# Relay_Driver.net
KiCad netlist of a schematic drawn in Altium Designer
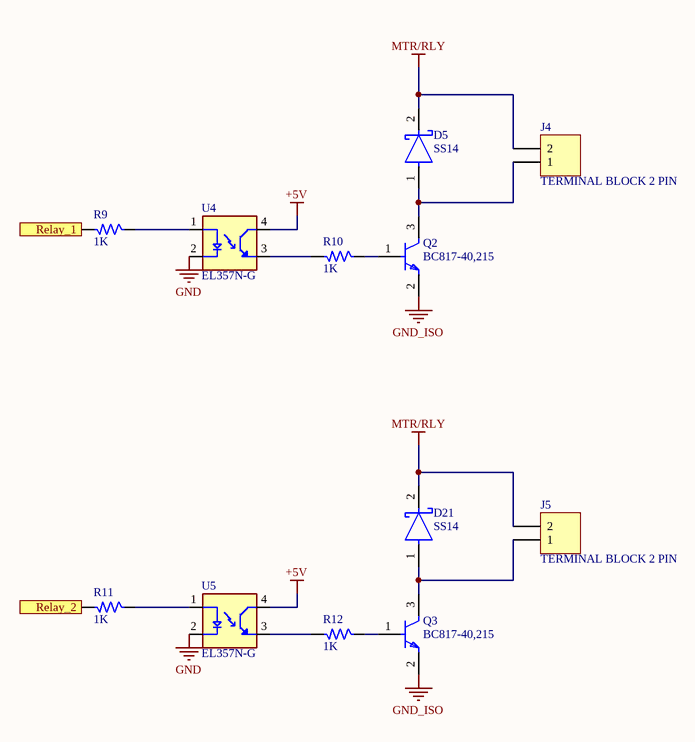
[diagram p0: Relay Driver.SchDoc]

(export (version "E")
  (design (tool "Eeschema 10.0.6"))
  (components
    (comp (ref "D5")
      (value "SS14")
      (footprint "FP-403AE-MFG")
      (description "DIODE SCHOTTKY 40V 1A SMA")
      (fields
        (field (name "MANUFACTURER") "ON Semiconductor")
        (field (name "OCTOPART") "https://octopart.com/ss14-on+semiconductor-29205033")
      )
      (libsource (lib "TAREKPCBLIB") (part "SS14"))
    )
    (comp (ref "D21")
      (value "SS14")
      (footprint "FP-403AE-MFG")
      (description "DIODE SCHOTTKY 40V 1A SMA")
      (fields
        (field (name "MANUFACTURER") "ON Semiconductor")
        (field (name "OCTOPART") "https://octopart.com/ss14-on+semiconductor-29205033")
      )
      (libsource (lib "TAREKPCBLIB") (part "SS14"))
    )
    (comp (ref "J4")
      (value "TERMINAL BLOCK 2 PIN")
      (footprint "CON2_P196_1729128_TH_ST")
      (description "2 Pins, 1 Row 5mm Pitch, straight Connector, male")
      (fields
        (field (name "MANUFACTURER") "Phoenix Contact")
        (field (name "MANUFACTURER PART NUMBER") "MKDSN1,5/2")
      )
      (libsource (lib "ESTEEMPCBLIB") (part "CON-TB_2X1-196-ST-TH"))
    )
    (comp (ref "J5")
      (value "TERMINAL BLOCK 2 PIN")
      (footprint "CON2_P196_1729128_TH_ST")
      (description "2 Pins, 1 Row 5mm Pitch, straight Connector, male")
      (fields
        (field (name "MANUFACTURER") "Phoenix Contact")
        (field (name "MANUFACTURER PART NUMBER") "MKDSN1,5/2")
      )
      (libsource (lib "ESTEEMPCBLIB") (part "CON-TB_2X1-196-ST-TH"))
    )
    (comp (ref "Q2")
      (value "BC817-40,215")
      (footprint "FP-SOT23-IPC_A")
      (description "TRANS NPN 45V 0.5A SOT23")
      (fields
        (field (name "OCTOPART") "https://octopart.com/bc817-40%2C215-nexperia-78739081")
        (field (name "MANUFACTURER") "Nexperia")
      )
      (libsource (lib "TAREKPCBLIB") (part "CMP-14406-000007-1"))
    )
    (comp (ref "Q3")
      (value "BC817-40,215")
      (footprint "FP-SOT23-IPC_A")
      (description "TRANS NPN 45V 0.5A SOT23")
      (fields
        (field (name "OCTOPART") "https://octopart.com/bc817-40%2C215-nexperia-78739081")
        (field (name "MANUFACTURER") "Nexperia")
      )
      (libsource (lib "TAREKPCBLIB") (part "CMP-14406-000007-1"))
    )
    (comp (ref "R9")
      (value "1K")
      (footprint "RES_0805")
      (description "1 kOhms ±1% 0.125W, 1/8W Chip Resistor 0805 (2012 Metric) Moisture Resistant Thick Film")
      (fields (field (name "MANUFACTURER") "Walsin") (field (name "MANUFACTURER PART NUMBER") "WR08X1001FTL"))
      (libsource (lib "ESTEEMPCBLIB") (part "RES_1K-0.125W-1%-0805"))
    )
    (comp (ref "R10")
      (value "1K")
      (footprint "RES_0805")
      (description "1 kOhms ±1% 0.125W, 1/8W Chip Resistor 0805 (2012 Metric) Moisture Resistant Thick Film")
      (fields (field (name "MANUFACTURER") "Walsin") (field (name "MANUFACTURER PART NUMBER") "WR08X1001FTL"))
      (libsource (lib "ESTEEMPCBLIB") (part "RES_1K-0.125W-1%-0805"))
    )
    (comp (ref "R11")
      (value "1K")
      (footprint "RES_0805")
      (description "1 kOhms ±1% 0.125W, 1/8W Chip Resistor 0805 (2012 Metric) Moisture Resistant Thick Film")
      (fields (field (name "MANUFACTURER") "Walsin") (field (name "MANUFACTURER PART NUMBER") "WR08X1001FTL"))
      (libsource (lib "ESTEEMPCBLIB") (part "RES_1K-0.125W-1%-0805"))
    )
    (comp (ref "R12")
      (value "1K")
      (footprint "RES_0805")
      (description "1 kOhms ±1% 0.125W, 1/8W Chip Resistor 0805 (2012 Metric) Moisture Resistant Thick Film")
      (fields (field (name "MANUFACTURER") "Walsin") (field (name "MANUFACTURER PART NUMBER") "WR08X1001FTL"))
      (libsource (lib "ESTEEMPCBLIB") (part "RES_1K-0.125W-1%-0805"))
    )
    (comp (ref "U4")
      (value "EL357N-G")
      (footprint "OPTO_EL357N-G")
      (description "PHOTOTRANSISTOR PHOTOCOUPLER")
      (libsource (lib "TAREKPCBLIB") (part "EL357N-G"))
    )
    (comp (ref "U5")
      (value "EL357N-G")
      (footprint "OPTO_EL357N-G")
      (description "PHOTOTRANSISTOR PHOTOCOUPLER")
      (libsource (lib "TAREKPCBLIB") (part "EL357N-G"))
    )
  )
  (nets
    (net (code "1") (name "+5V") (class "Default")
      (node (ref "U4") (pin "4") (pinfunction "CT_4") (pintype "passive"))
      (node (ref "U5") (pin "4") (pinfunction "CT_4") (pintype "passive"))
    )
    (net (code "2") (name "/Relay_1") (class "Default")
      (node (ref "R9") (pin "2") (pinfunction "2_2") (pintype "passive"))
    )
    (net (code "3") (name "/Relay_2") (class "Default")
      (node (ref "R11") (pin "2") (pinfunction "2_2") (pintype "passive"))
    )
    (net (code "4") (name "GND") (class "Default")
      (node (ref "U4") (pin "2") (pinfunction "C_2") (pintype "passive"))
      (node (ref "U5") (pin "2") (pinfunction "C_2") (pintype "passive"))
    )
    (net (code "5") (name "GND_ISO") (class "Default")
      (node (ref "Q2") (pin "2") (pinfunction "E_2") (pintype "passive"))
      (node (ref "Q3") (pin "2") (pinfunction "E_2") (pintype "passive"))
    )
    (net (code "6") (name "MTR{slash}RLY") (class "Default")
      (node (ref "D21") (pin "2") (pinfunction "C_2") (pintype "passive"))
      (node (ref "D5") (pin "2") (pinfunction "C_2") (pintype "passive"))
      (node (ref "J4") (pin "2") (pinfunction "2_2") (pintype "passive"))
      (node (ref "J5") (pin "2") (pinfunction "2_2") (pintype "passive"))
    )
    (net (code "7") (name "Net-(D5-A)") (class "Default")
      (node (ref "D5") (pin "1") (pinfunction "A_1") (pintype "passive"))
      (node (ref "J4") (pin "1") (pinfunction "1_1") (pintype "passive"))
      (node (ref "Q2") (pin "3") (pinfunction "C_3") (pintype "passive"))
    )
    (net (code "8") (name "Net-(D21-A)") (class "Default")
      (node (ref "D21") (pin "1") (pinfunction "A_1") (pintype "passive"))
      (node (ref "J5") (pin "1") (pinfunction "1_1") (pintype "passive"))
      (node (ref "Q3") (pin "3") (pinfunction "C_3") (pintype "passive"))
    )
    (net (code "9") (name "Net-(Q2-B)") (class "Default")
      (node (ref "Q2") (pin "1") (pinfunction "B_1") (pintype "passive"))
      (node (ref "R10") (pin "1") (pinfunction "1_1") (pintype "passive"))
    )
    (net (code "10") (name "Net-(Q3-B)") (class "Default")
      (node (ref "Q3") (pin "1") (pinfunction "B_1") (pintype "passive"))
      (node (ref "R12") (pin "1") (pinfunction "1_1") (pintype "passive"))
    )
    (net (code "11") (name "Net-(U4-A)") (class "Default")
      (node (ref "R9") (pin "1") (pinfunction "1_1") (pintype "passive"))
      (node (ref "U4") (pin "1") (pinfunction "A_1") (pintype "passive"))
    )
    (net (code "12") (name "Net-(U4-ET)") (class "Default")
      (node (ref "R10") (pin "2") (pinfunction "2_2") (pintype "passive"))
      (node (ref "U4") (pin "3") (pinfunction "ET_3") (pintype "passive"))
    )
    (net (code "13") (name "Net-(U5-A)") (class "Default")
      (node (ref "R11") (pin "1") (pinfunction "1_1") (pintype "passive"))
      (node (ref "U5") (pin "1") (pinfunction "A_1") (pintype "passive"))
    )
    (net (code "14") (name "Net-(U5-ET)") (class "Default")
      (node (ref "R12") (pin "2") (pinfunction "2_2") (pintype "passive"))
      (node (ref "U5") (pin "3") (pinfunction "ET_3") (pintype "passive"))
    )
  )
)
